# Camera_sdcard.net
KiCad netlist of a schematic drawn in Altium Designer
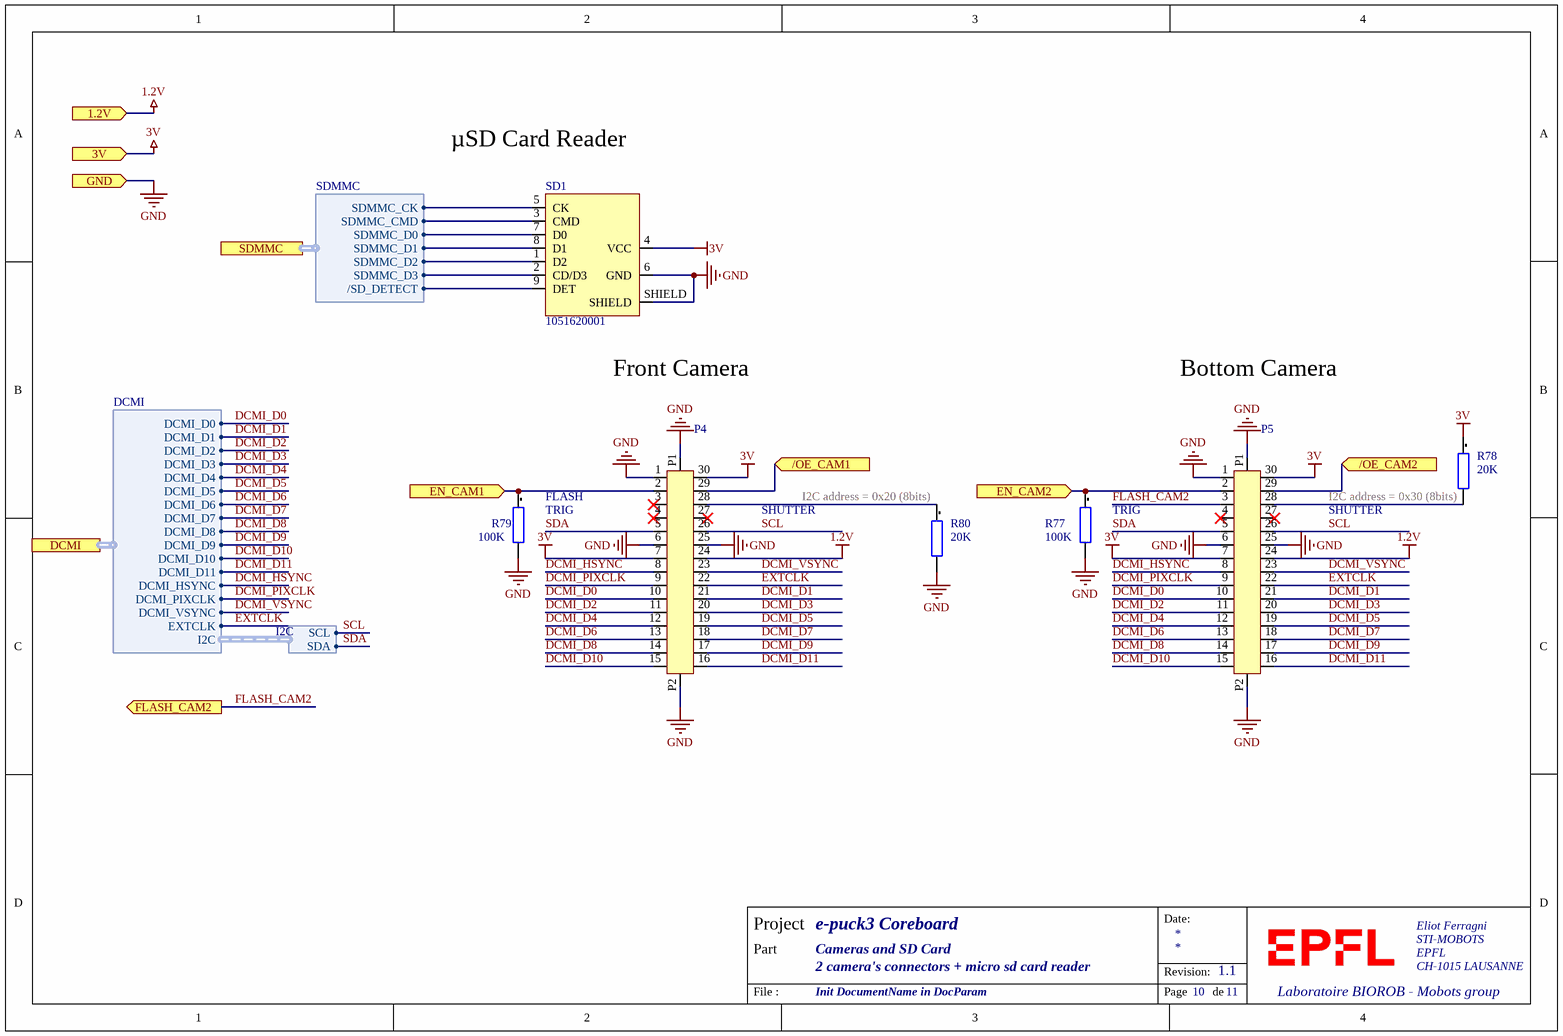
[diagram p0: Camera_sdcard.SchDoc]

(export (version "E")
  (design (tool "Eeschema 10.0.6"))
  (components
    (comp (ref "P4")
      (value "HIROSE_BM23FR0.6-30DS-0.35V")
      (footprint "HIROSE_BM23FR0.6-30DS-0.35V")
      (fields
        (field (name "MANUFACTURER") "Hirose")
        (field (name "MANUFACTURER PART NUMBER") "BM23FR0.6-30DS-0.35V(895)")
      )
      (libsource (lib "LSRO1Altium") (part "Con2X15B-2P"))
    )
    (comp (ref "P5")
      (value "HIROSE_BM23FR0.6-30DS-0.35V")
      (footprint "HIROSE_BM23FR0.6-30DS-0.35V")
      (fields
        (field (name "MANUFACTURER") "Hirose")
        (field (name "MANUFACTURER PART NUMBER") "BM23FR0.6-30DS-0.35V(895)")
      )
      (libsource (lib "LSRO1Altium") (part "Con2X15B-2P"))
    )
    (comp (ref "R77")
      (value "100K")
      (footprint "RESC0201(0603)_L")
      (description "Resistor 0201")
      (libsource (lib "LSRO1Altium") (part "RES"))
    )
    (comp (ref "R78")
      (value "20K")
      (footprint "RESC0201(0603)_L")
      (description "Resistor 0201")
      (libsource (lib "LSRO1Altium") (part "RES"))
    )
    (comp (ref "R79")
      (value "100K")
      (footprint "RESC0201(0603)_L")
      (description "Resistor 0201")
      (libsource (lib "LSRO1Altium") (part "RES"))
    )
    (comp (ref "R80")
      (value "20K")
      (footprint "RESC0201(0603)_L")
      (description "Resistor 0201")
      (libsource (lib "LSRO1Altium") (part "RES"))
    )
    (comp (ref "SD1")
      (value "1051620001")
      (footprint "1051620001-with_card")
      (description "Conn Micro SD Card HDR 8 POS 1.09mm Solder RA SMD Embossed T/R 0.5A")
      (fields (field (name "MANUFACTURER") "Molex") (field (name "MANUFACTURER PART NUMBER") "1051620001"))
      (libsource (lib "Schlib") (part "1051620001"))
    )
  )
  (nets
    (net (code "4") (name "/DCMI_D0") (class "Default")
      (node (ref "P4") (pin "10") (pinfunction "10_10") (pintype "passive"))
      (node (ref "P5") (pin "10") (pinfunction "10_10") (pintype "passive"))
    )
    (net (code "5") (name "/DCMI_D1") (class "Default")
      (node (ref "P4") (pin "21") (pinfunction "21_21") (pintype "passive"))
      (node (ref "P5") (pin "21") (pinfunction "21_21") (pintype "passive"))
    )
    (net (code "6") (name "/DCMI_D2") (class "Default")
      (node (ref "P4") (pin "11") (pinfunction "11_11") (pintype "passive"))
      (node (ref "P5") (pin "11") (pinfunction "11_11") (pintype "passive"))
    )
    (net (code "7") (name "/DCMI_D3") (class "Default")
      (node (ref "P4") (pin "20") (pinfunction "20_20") (pintype "passive"))
      (node (ref "P5") (pin "20") (pinfunction "20_20") (pintype "passive"))
    )
    (net (code "8") (name "/DCMI_D4") (class "Default")
      (node (ref "P4") (pin "12") (pinfunction "12_12") (pintype "passive"))
      (node (ref "P5") (pin "12") (pinfunction "12_12") (pintype "passive"))
    )
    (net (code "9") (name "/DCMI_D5") (class "Default")
      (node (ref "P4") (pin "19") (pinfunction "19_19") (pintype "passive"))
      (node (ref "P5") (pin "19") (pinfunction "19_19") (pintype "passive"))
    )
    (net (code "10") (name "/DCMI_D6") (class "Default")
      (node (ref "P4") (pin "13") (pinfunction "13_13") (pintype "passive"))
      (node (ref "P5") (pin "13") (pinfunction "13_13") (pintype "passive"))
    )
    (net (code "11") (name "/DCMI_D7") (class "Default")
      (node (ref "P4") (pin "18") (pinfunction "18_18") (pintype "passive"))
      (node (ref "P5") (pin "18") (pinfunction "18_18") (pintype "passive"))
    )
    (net (code "12") (name "/DCMI_D8") (class "Default")
      (node (ref "P4") (pin "14") (pinfunction "14_14") (pintype "passive"))
      (node (ref "P5") (pin "14") (pinfunction "14_14") (pintype "passive"))
    )
    (net (code "13") (name "/DCMI_D9") (class "Default")
      (node (ref "P4") (pin "17") (pinfunction "17_17") (pintype "passive"))
      (node (ref "P5") (pin "17") (pinfunction "17_17") (pintype "passive"))
    )
    (net (code "14") (name "/DCMI_D10") (class "Default")
      (node (ref "P4") (pin "15") (pinfunction "15_15") (pintype "passive"))
      (node (ref "P5") (pin "15") (pinfunction "15_15") (pintype "passive"))
    )
    (net (code "15") (name "/DCMI_D11") (class "Default")
      (node (ref "P4") (pin "16") (pinfunction "16_16") (pintype "passive"))
      (node (ref "P5") (pin "16") (pinfunction "16_16") (pintype "passive"))
    )
    (net (code "16") (name "/DCMI_HSYNC") (class "Default")
      (node (ref "P4") (pin "8") (pinfunction "8_8") (pintype "passive"))
      (node (ref "P5") (pin "8") (pinfunction "8_8") (pintype "passive"))
    )
    (net (code "17") (name "/DCMI_PIXCLK") (class "Default")
      (node (ref "P4") (pin "9") (pinfunction "9_9") (pintype "passive"))
      (node (ref "P5") (pin "9") (pinfunction "9_9") (pintype "passive"))
    )
    (net (code "18") (name "/DCMI_VSYNC") (class "Default")
      (node (ref "P4") (pin "23") (pinfunction "23_23") (pintype "passive"))
      (node (ref "P5") (pin "23") (pinfunction "23_23") (pintype "passive"))
    )
    (net (code "20") (name "/EN_CAM1") (class "Default")
      (node (ref "P4") (pin "2") (pinfunction "2_2") (pintype "passive"))
      (node (ref "R79") (pin "1") (pinfunction "1_1") (pintype "passive"))
    )
    (net (code "21") (name "/EN_CAM2") (class "Default")
      (node (ref "P5") (pin "2") (pinfunction "2_2") (pintype "passive"))
      (node (ref "R77") (pin "1") (pinfunction "1_1") (pintype "passive"))
    )
    (net (code "22") (name "/EXTCLK") (class "Default")
      (node (ref "P4") (pin "22") (pinfunction "22_22") (pintype "passive"))
      (node (ref "P5") (pin "22") (pinfunction "22_22") (pintype "passive"))
    )
    (net (code "23") (name "/FLASH_CAM2") (class "Default")
      (node (ref "P5") (pin "3") (pinfunction "3_3") (pintype "passive"))
    )
    (net (code "24") (name "/SCL") (class "Default")
      (node (ref "P4") (pin "26") (pinfunction "26_26") (pintype "passive"))
      (node (ref "P5") (pin "26") (pinfunction "26_26") (pintype "passive"))
    )
    (net (code "25") (name "/SDA") (class "Default")
      (node (ref "P4") (pin "5") (pinfunction "5_5") (pintype "passive"))
      (node (ref "P5") (pin "5") (pinfunction "5_5") (pintype "passive"))
    )
    (net (code "28") (name "/{slash}OE_CAM1") (class "Default")
      (node (ref "P4") (pin "29") (pinfunction "29_29") (pintype "passive"))
    )
    (net (code "29") (name "/{slash}OE_CAM2") (class "Default")
      (node (ref "P5") (pin "29") (pinfunction "29_29") (pintype "passive"))
    )
    (net (code "30") (name "1.2V") (class "Default")
      (node (ref "P4") (pin "24") (pinfunction "24_24") (pintype "passive"))
      (node (ref "P5") (pin "24") (pinfunction "24_24") (pintype "passive"))
    )
    (net (code "31") (name "3V") (class "Default")
      (node (ref "P4") (pin "30") (pinfunction "30_30") (pintype "passive"))
      (node (ref "P4") (pin "7") (pinfunction "7_7") (pintype "passive"))
      (node (ref "P5") (pin "30") (pinfunction "30_30") (pintype "passive"))
      (node (ref "P5") (pin "7") (pinfunction "7_7") (pintype "passive"))
      (node (ref "R78") (pin "1") (pinfunction "1_1") (pintype "passive"))
      (node (ref "SD1") (pin "4") (pinfunction "VCC_4") (pintype "passive"))
    )
    (net (code "32") (name "GND") (class "Default")
      (node (ref "P4") (pin "1") (pinfunction "1_1") (pintype "passive"))
      (node (ref "P4") (pin "25") (pinfunction "25_25") (pintype "passive"))
      (node (ref "P4") (pin "6") (pinfunction "6_6") (pintype "passive"))
      (node (ref "P4") (pin "P1") (pinfunction "P1_P1") (pintype "passive"))
      (node (ref "P4") (pin "P2") (pinfunction "P2_P2") (pintype "passive"))
      (node (ref "P5") (pin "1") (pinfunction "1_1") (pintype "passive"))
      (node (ref "P5") (pin "25") (pinfunction "25_25") (pintype "passive"))
      (node (ref "P5") (pin "6") (pinfunction "6_6") (pintype "passive"))
      (node (ref "P5") (pin "P1") (pinfunction "P1_P1") (pintype "passive"))
      (node (ref "P5") (pin "P2") (pinfunction "P2_P2") (pintype "passive"))
      (node (ref "R77") (pin "2") (pinfunction "2_2") (pintype "passive"))
      (node (ref "R79") (pin "2") (pinfunction "2_2") (pintype "passive"))
      (node (ref "R80") (pin "2") (pinfunction "2_2") (pintype "passive"))
      (node (ref "SD1") (pin "6") (pinfunction "GND_6") (pintype "passive"))
      (node (ref "SD1") (pin "SHIELD") (pinfunction "SHIELD_SHIELD") (pintype "passive"))
    )
    (net (code "33") (name "Net-(P4-Pad28)") (class "Default")
      (node (ref "P4") (pin "28") (pinfunction "28_28") (pintype "passive"))
      (node (ref "R80") (pin "1") (pinfunction "1_1") (pintype "passive"))
    )
    (net (code "34") (name "Net-(P5-Pad28)") (class "Default")
      (node (ref "P5") (pin "28") (pinfunction "28_28") (pintype "passive"))
      (node (ref "R78") (pin "2") (pinfunction "2_2") (pintype "passive"))
    )
    (net (code "35") (name "unconnected-(P4-Pad3)") (class "Default")
      (node (ref "P4") (pin "3") (pinfunction "3_3") (pintype "passive+no_connect"))
    )
    (net (code "36") (name "unconnected-(P4-Pad4)") (class "Default")
      (node (ref "P4") (pin "4") (pinfunction "4_4") (pintype "passive+no_connect"))
    )
    (net (code "37") (name "unconnected-(P4-Pad27)") (class "Default")
      (node (ref "P4") (pin "27") (pinfunction "27_27") (pintype "passive+no_connect"))
    )
    (net (code "38") (name "unconnected-(P5-Pad4)") (class "Default")
      (node (ref "P5") (pin "4") (pinfunction "4_4") (pintype "passive+no_connect"))
    )
    (net (code "39") (name "unconnected-(P5-Pad27)") (class "Default")
      (node (ref "P5") (pin "27") (pinfunction "27_27") (pintype "passive+no_connect"))
    )
    (net (code "40") (name "unconnected-(SD1-CD{slash}D3-Pad2)") (class "Default")
      (node (ref "SD1") (pin "2") (pinfunction "CD/D3_2") (pintype "passive"))
    )
    (net (code "41") (name "unconnected-(SD1-CK-Pad5)") (class "Default")
      (node (ref "SD1") (pin "5") (pinfunction "CK_5") (pintype "passive"))
    )
    (net (code "42") (name "unconnected-(SD1-CMD-Pad3)") (class "Default")
      (node (ref "SD1") (pin "3") (pinfunction "CMD_3") (pintype "passive"))
    )
    (net (code "43") (name "unconnected-(SD1-D0-Pad7)") (class "Default")
      (node (ref "SD1") (pin "7") (pinfunction "D0_7") (pintype "passive"))
    )
    (net (code "44") (name "unconnected-(SD1-D1-Pad8)") (class "Default")
      (node (ref "SD1") (pin "8") (pinfunction "D1_8") (pintype "passive"))
    )
    (net (code "45") (name "unconnected-(SD1-D2-Pad1)") (class "Default")
      (node (ref "SD1") (pin "1") (pinfunction "D2_1") (pintype "passive"))
    )
    (net (code "46") (name "unconnected-(SD1-DET-Pad9)") (class "Default")
      (node (ref "SD1") (pin "9") (pinfunction "DET_9") (pintype "passive"))
    )
  )
)
